# Power_Regulation_and_Protection.net
KiCad netlist of a schematic drawn in Altium Designer
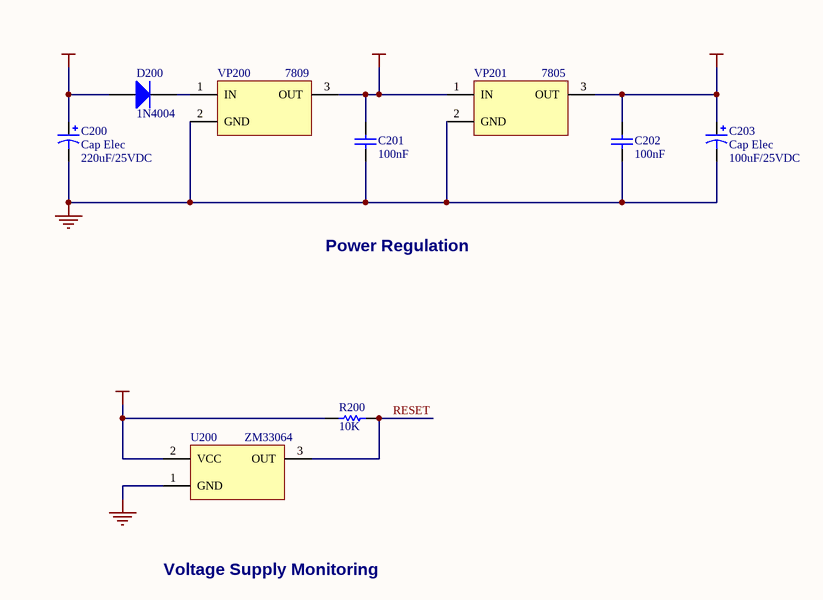
[diagram p0: Power Regulation and Protection.SCHDOC]

(export (version "E")
  (design (tool "Eeschema 10.0.6"))
  (components
    (comp (ref "C200")
      (value "Cap Elec")
      (footprint "CAPR5-4X5")
      (description "Polarized Capacitor (Axial)")
      (fields (field (name "ALTIUM_VALUE") "220uF/25VDC") (field (name "PUBLISHER") "Altium Limited"))
      (libsource (lib "Miscellaneous Devices") (part "Cap Pol2"))
    )
    (comp (ref "C201")
      (value "100nF")
      (footprint "BCY-W2/D3.1")
      (description "Capacitor")
      (fields (field (name "PUBLISHER") "Altium Limited"))
      (libsource (lib "Miscellaneous Devices") (part "Cap"))
    )
    (comp (ref "C202")
      (value "100nF")
      (footprint "BCY-W2/D3.1")
      (description "Capacitor")
      (fields (field (name "PUBLISHER") "Altium Limited"))
      (libsource (lib "Miscellaneous Devices") (part "Cap"))
    )
    (comp (ref "C203")
      (value "Cap Elec")
      (footprint "CAPR5-4X5")
      (description "Polarized Capacitor (Axial)")
      (fields (field (name "ALTIUM_VALUE") "100uF/25VDC") (field (name "PUBLISHER") "Altium Limited"))
      (libsource (lib "Miscellaneous Devices") (part "Cap Pol2"))
    )
    (comp (ref "D200")
      (value "1N4004")
      (footprint "DIO10.46-5.3x2.8")
      (description "1 Amp General Purpose Rectifier")
      (fields (field (name "PUBLISHER") "Altium Limited"))
      (libsource (lib "Miscellaneous Devices") (part "Diode 1N4004"))
    )
    (comp (ref "R200")
      (value "10K")
      (footprint "AXIAL-0.3")
      (description "Resistor")
      (fields (field (name "PUBLISHER") "Altium Limited"))
      (libsource (lib "Miscellaneous Devices") (part "Res1"))
    )
    (comp (ref "U200")
      (value "ZM33064")
      (footprint "BCY-W3")
      (description "Generic 5V Supply Voltage Monitor")
      (libsource (lib "Schematic Library") (part "ZM33064"))
    )
    (comp (ref "VP200")
      (value "7809")
      (footprint "PIN3")
      (description "Generic 9V Voltage Regulator")
      (libsource (lib "Schematic Library") (part "7809"))
    )
    (comp (ref "VP201")
      (value "7805")
      (footprint "PIN3")
      (description "Generic 6V Voltage Regulator")
      (libsource (lib "Schematic Library") (part "7805"))
    )
  )
  (nets
    (net (code "1") (name "/RESET") (class "Default")
      (node (ref "R200") (pin "1") (pinfunction "1_1") (pintype "passive"))
      (node (ref "U200") (pin "3") (pinfunction "OUT_3") (pintype "passive"))
    )
    (net (code "2") (name "5V") (class "Default")
      (node (ref "C202") (pin "2") (pinfunction "2_2") (pintype "passive"))
      (node (ref "C203") (pin "1") (pinfunction "1_1") (pintype "passive"))
      (node (ref "R200") (pin "2") (pinfunction "2_2") (pintype "passive"))
      (node (ref "U200") (pin "2") (pinfunction "VCC_2") (pintype "passive"))
      (node (ref "VP201") (pin "3") (pinfunction "OUT_3") (pintype "passive"))
    )
    (net (code "3") (name "9V") (class "Default")
      (node (ref "C201") (pin "2") (pinfunction "2_2") (pintype "passive"))
      (node (ref "VP200") (pin "3") (pinfunction "OUT_3") (pintype "passive"))
      (node (ref "VP201") (pin "1") (pinfunction "IN_1") (pintype "passive"))
    )
    (net (code "4") (name "10-12V IN") (class "Default")
      (node (ref "C200") (pin "1") (pinfunction "1_1") (pintype "passive"))
      (node (ref "D200") (pin "1") (pinfunction "A_1") (pintype "passive"))
    )
    (net (code "5") (name "GND") (class "Default")
      (node (ref "C200") (pin "2") (pinfunction "2_2") (pintype "passive"))
      (node (ref "C201") (pin "1") (pinfunction "1_1") (pintype "passive"))
      (node (ref "C202") (pin "1") (pinfunction "1_1") (pintype "passive"))
      (node (ref "C203") (pin "2") (pinfunction "2_2") (pintype "passive"))
      (node (ref "U200") (pin "1") (pinfunction "GND_1") (pintype "passive"))
      (node (ref "VP200") (pin "2") (pinfunction "GND_2") (pintype "passive"))
      (node (ref "VP201") (pin "2") (pinfunction "GND_2") (pintype "passive"))
    )
    (net (code "6") (name "Net-(D200-K)") (class "Default")
      (node (ref "D200") (pin "2") (pinfunction "K_2") (pintype "passive"))
      (node (ref "VP200") (pin "1") (pinfunction "IN_1") (pintype "passive"))
    )
  )
)
